# bjt.net
KiCad netlist of a schematic drawn in EAGLE
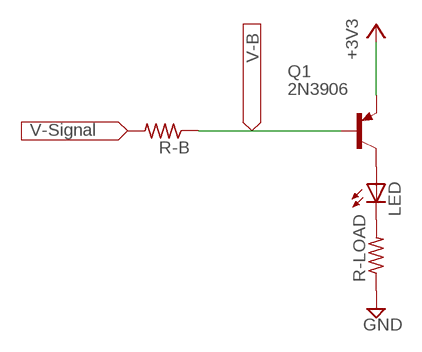
[diagram p0: schematic, sheet 1]

(export (version "E")
  (design (tool "Eeschema 10.0.6"))
  (components
    (comp (ref "LED")
      (value "LED5MM")
      (footprint "eagle-import:LED5MM")
      (libsource (lib "eagle-import") (part "LED5MM"))
    )
    (comp (ref "Q1")
      (value "2N3906")
      (footprint "eagle-import:TO92")
      (libsource (lib "eagle-import") (part "2N3906"))
    )
    (comp (ref "R-B")
      (value "R-US_0411/12")
      (footprint "eagle-import:0411_12")
      (libsource (lib "eagle-import") (part "R-US_0411/12"))
    )
    (comp (ref "R-LOAD")
      (value "R-US_0411/12")
      (footprint "eagle-import:0411_12")
      (libsource (lib "eagle-import") (part "R-US_0411/12"))
    )
  )
  (nets
    (net (code "1") (name "+3V3") (class "Default")
      (node (ref "Q1") (pin "3") (pinfunction "E_3") (pintype "passive"))
    )
    (net (code "2") (name "GND") (class "Default")
      (node (ref "R-LOAD") (pin "1") (pinfunction "1_1") (pintype "passive"))
    )
    (net (code "3") (name "Net-(LED-C)") (class "Default")
      (node (ref "LED") (pin "K") (pinfunction "C_K") (pintype "passive"))
      (node (ref "R-LOAD") (pin "2") (pinfunction "2_2") (pintype "passive"))
    )
    (net (code "4") (name "Net-(Q1-B)") (class "Default")
      (node (ref "Q1") (pin "2") (pinfunction "B_2") (pintype "passive"))
      (node (ref "R-B") (pin "1") (pinfunction "1_1") (pintype "passive"))
    )
    (net (code "5") (name "Net-(Q1-C)") (class "Default")
      (node (ref "LED") (pin "A") (pinfunction "A_A") (pintype "passive"))
      (node (ref "Q1") (pin "1") (pinfunction "C_1") (pintype "passive"))
    )
    (net (code "6") (name "unconnected-(R-B-Pad2)") (class "Default")
      (node (ref "R-B") (pin "2") (pinfunction "2_2") (pintype "passive"))
    )
  )
)
